# openSX70_ALADDIN_V36_20180117.net
KiCad netlist of a schematic drawn in EAGLE
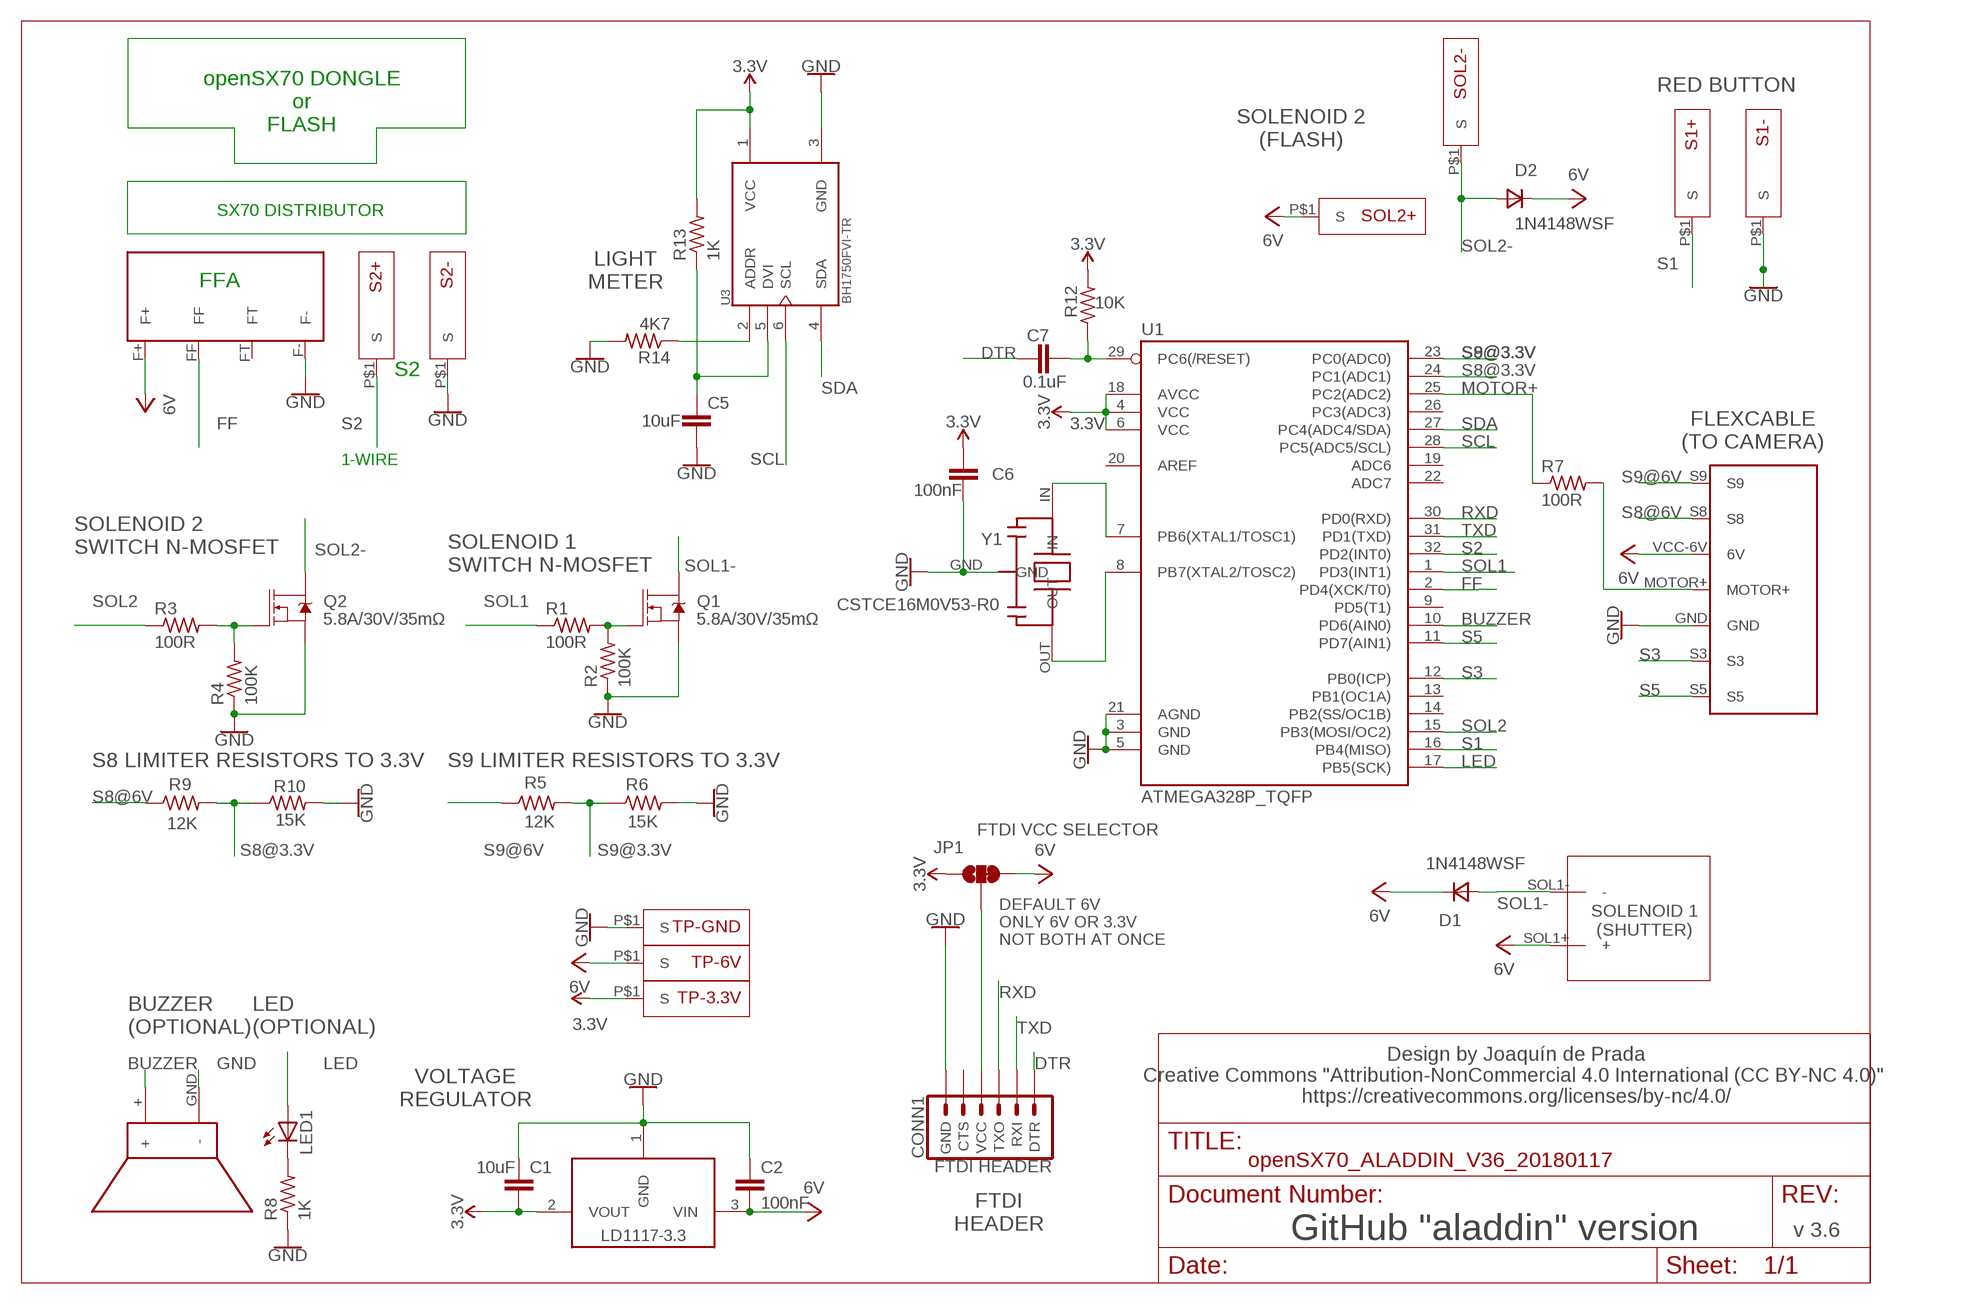
[diagram p0: schematic, sheet 1]

(export (version "E")
  (design (tool "Eeschema 10.0.6"))
  (components
    (comp (ref "BUZZ1")
      (value "CSET8-5G")
      (footprint "eagle-import:CSET8-5G_PACKAGE")
      (libsource (lib "eagle-import") (part "CSET8-5G"))
    )
    (comp (ref "C1")
      (value "10uF")
      (footprint "eagle-import:0603")
      (libsource (lib "eagle-import") (part "10UF-0603-6.3V-20%"))
    )
    (comp (ref "C2")
      (value "100nF")
      (footprint "eagle-import:C0603K")
      (libsource (lib "eagle-import") (part "C-EUC0603K"))
    )
    (comp (ref "C5")
      (value "10uF")
      (footprint "eagle-import:0603")
      (libsource (lib "eagle-import") (part "10UF-0603-6.3V-20%"))
    )
    (comp (ref "C6")
      (value "100nF")
      (footprint "eagle-import:C0805")
      (libsource (lib "eagle-import") (part "resistor_C-EUC0805"))
    )
    (comp (ref "C7")
      (value "0.1uF")
      (footprint "eagle-import:0603")
      (libsource (lib "eagle-import") (part "0.1UF-0603-25V-(+80/-20%)"))
    )
    (comp (ref "CONN1")
      (value "FTDI HEADER")
      (footprint "eagle-import:1X06")
      (libsource (lib "eagle-import") (part "6_PIN_SERIAL_TARGET"))
    )
    (comp (ref "D1")
      (value "1N4148WSF")
      (footprint "eagle-import:SOD323")
      (fields (field (name "MPN") "CDSOD323-T05C"))
      (libsource (lib "eagle-import") (part "DSOD323"))
    )
    (comp (ref "D2")
      (value "1N4148WSF")
      (footprint "eagle-import:SOD323")
      (fields (field (name "MPN") "CDSOD323-T05C"))
      (libsource (lib "eagle-import") (part "DSOD323"))
    )
    (comp (ref "JP1")
      (value "FTDI VCC SELECTOR")
      (footprint "eagle-import:SMT-JUMPER_3_1-NC_TRACE_SILK")
      (libsource (lib "eagle-import") (part "JUMPER-SMT_3_1-NC_TRACE_SILK"))
    )
    (comp (ref "LD11173.3V")
      (value "LD1117 3.3V")
      (footprint "eagle-import:SOT223")
      (fields (field (name "MF") "Advanced Monolithic Systems") (field (name "MP") "AMS1117-5.0"))
      (libsource (lib "eagle-import") (part "LD1117-3.3"))
    )
    (comp (ref "LED1")
      (value "LEDCHIPLED_0805")
      (footprint "eagle-import:CHIPLED_0805")
      (libsource (lib "eagle-import") (part "LEDCHIPLED_0805"))
    )
    (comp (ref "Q1")
      (value "5.8A/30V/35mΩ")
      (footprint "eagle-import:SOT23-3")
      (libsource (lib "eagle-import") (part "MOSFET-NCH-AO3404A"))
    )
    (comp (ref "Q2")
      (value "5.8A/30V/35mΩ")
      (footprint "eagle-import:SOT23-3")
      (libsource (lib "eagle-import") (part "MOSFET-NCH-AO3404A"))
    )
    (comp (ref "R1")
      (value "100R")
      (footprint "eagle-import:R0603")
      (libsource (lib "eagle-import") (part "R-US_R0603"))
    )
    (comp (ref "R2")
      (value "100K")
      (footprint "eagle-import:R0603")
      (libsource (lib "eagle-import") (part "R-US_R0603"))
    )
    (comp (ref "R3")
      (value "100R")
      (footprint "eagle-import:R0603")
      (libsource (lib "eagle-import") (part "R-US_R0603"))
    )
    (comp (ref "R4")
      (value "100K")
      (footprint "eagle-import:R0603")
      (libsource (lib "eagle-import") (part "R-US_R0603"))
    )
    (comp (ref "R5")
      (value "12K")
      (footprint "eagle-import:R0603")
      (libsource (lib "eagle-import") (part "R-US_R0603"))
    )
    (comp (ref "R6")
      (value "15K")
      (footprint "eagle-import:R0603")
      (libsource (lib "eagle-import") (part "R-US_R0603"))
    )
    (comp (ref "R7")
      (value "100R")
      (footprint "eagle-import:R0603")
      (libsource (lib "eagle-import") (part "R-US_R0603"))
    )
    (comp (ref "R8")
      (value "1K")
      (footprint "eagle-import:R0603")
      (libsource (lib "eagle-import") (part "R-US_R0603"))
    )
    (comp (ref "R9")
      (value "12K")
      (footprint "eagle-import:R0603")
      (libsource (lib "eagle-import") (part "R-US_R0603"))
    )
    (comp (ref "R10")
      (value "15K")
      (footprint "eagle-import:R0603")
      (libsource (lib "eagle-import") (part "R-US_R0603"))
    )
    (comp (ref "R12")
      (value "10K")
      (footprint "eagle-import:R0603")
      (libsource (lib "eagle-import") (part "R-US_R0603"))
    )
    (comp (ref "R13")
      (value "1K")
      (footprint "eagle-import:R0603")
      (libsource (lib "eagle-import") (part "R-US_R0603"))
    )
    (comp (ref "R14")
      (value "4K7")
      (footprint "eagle-import:R0603")
      (libsource (lib "eagle-import") (part "R-US_R0603"))
    )
    (comp (ref "S1+")
      (value "SX70-S-PAD-NEW")
      (footprint "eagle-import:SX70-S-PAD2")
      (libsource (lib "eagle-import") (part "SX70-S-PAD-NEW"))
    )
    (comp (ref "S1-")
      (value "SX70-S-PAD-NEW")
      (footprint "eagle-import:SX70-S-PAD2")
      (libsource (lib "eagle-import") (part "SX70-S-PAD-NEW"))
    )
    (comp (ref "S2+")
      (value "SX70-S-PAD-NEW")
      (footprint "eagle-import:SX70-S-PAD2")
      (libsource (lib "eagle-import") (part "SX70-S-PAD-NEW"))
    )
    (comp (ref "S2-")
      (value "SX70-S-PAD-NEW")
      (footprint "eagle-import:SX70-S-PAD2")
      (libsource (lib "eagle-import") (part "SX70-S-PAD-NEW"))
    )
    (comp (ref "SOL1")
      (value "SX70-SOLENOID1-2PADS")
      (footprint "eagle-import:SX70-SOLENOID1-2")
      (libsource (lib "eagle-import") (part "SX70-SOLENOID1-2PADS"))
    )
    (comp (ref "SOL2+")
      (value "SX70-S-PAD-NEW")
      (footprint "eagle-import:SX70-S-PAD2")
      (libsource (lib "eagle-import") (part "SX70-S-PAD-NEW"))
    )
    (comp (ref "SOL2-")
      (value "SX70-S-PAD-NEW")
      (footprint "eagle-import:SX70-S-PAD2")
      (libsource (lib "eagle-import") (part "SX70-S-PAD-NEW"))
    )
    (comp (ref "TP-3.3V")
      (value "SX70-S-PAD-NEW")
      (footprint "eagle-import:SX70-S-PAD2")
      (libsource (lib "eagle-import") (part "SX70-S-PAD-NEW"))
    )
    (comp (ref "TP-6V")
      (value "SX70-S-PAD-NEW")
      (footprint "eagle-import:SX70-S-PAD2")
      (libsource (lib "eagle-import") (part "SX70-S-PAD-NEW"))
    )
    (comp (ref "TP-GND")
      (value "SX70-S-PAD-NEW")
      (footprint "eagle-import:SX70-S-PAD2")
      (libsource (lib "eagle-import") (part "SX70-S-PAD-NEW"))
    )
    (comp (ref "U$1")
      (value "SX70-7-PAD")
      (footprint "eagle-import:SX70-7-PAD")
      (libsource (lib "eagle-import") (part "SX70-7-PAD"))
    )
    (comp (ref "U$2")
      (value "FFA")
      (footprint "eagle-import:FFA-PAD-PACKAGE")
      (libsource (lib "eagle-import") (part "SX70-FFA-PAD"))
    )
    (comp (ref "U1")
      (value "ATMEGA328P_TQFP")
      (footprint "eagle-import:TQFP32-08")
      (libsource (lib "eagle-import") (part "ATMEGA328P_TQFP"))
    )
    (comp (ref "U3")
      (value "BH1750FVI-TR")
      (footprint "eagle-import:SOTFL50P300X75-6N")
      (fields (field (name "MF") "Rohm"))
      (libsource (lib "eagle-import") (part "BH1750FVI-TR"))
    )
    (comp (ref "Y1")
      (value "CSTCE16M0V53-R0")
      (footprint "eagle-import:CFP95P160X100-3N")
      (fields (field (name "MF") "Murata"))
      (libsource (lib "eagle-import") (part "CSTCE16M0V53-R0"))
    )
  )
  (nets
    (net (code "1") (name "/BUZZER") (class "Default")
      (node (ref "BUZZ1") (pin "+") (pinfunction "+_+") (pintype "bidirectional"))
      (node (ref "U1") (pin "10") (pinfunction "PD6(AIN0)_10") (pintype "bidirectional"))
    )
    (net (code "2") (name "/DTR") (class "Default")
      (node (ref "C7") (pin "1") (pinfunction "1_1") (pintype "passive"))
      (node (ref "CONN1") (pin "1") (pinfunction "DTR_1") (pintype "passive"))
    )
    (net (code "3") (name "/FF") (class "Default")
      (node (ref "U$2") (pin "FF") (pinfunction "FF_FF") (pintype "bidirectional"))
      (node (ref "U1") (pin "2") (pinfunction "PD4(XCK/T0)_2") (pintype "bidirectional"))
    )
    (net (code "4") (name "/LED") (class "Default")
      (node (ref "LED1") (pin "A") (pinfunction "A_A") (pintype "passive"))
      (node (ref "U1") (pin "17") (pinfunction "PB5(SCK)_17") (pintype "bidirectional"))
    )
    (net (code "5") (name "/MOTOR+") (class "Default")
      (node (ref "R7") (pin "1") (pinfunction "1_1") (pintype "passive"))
      (node (ref "U1") (pin "25") (pinfunction "PC2(ADC2)_25") (pintype "bidirectional"))
    )
    (net (code "6") (name "/RXD") (class "Default")
      (node (ref "CONN1") (pin "3") (pinfunction "TXO_3") (pintype "passive"))
      (node (ref "U1") (pin "30") (pinfunction "PD0(RXD)_30") (pintype "bidirectional"))
    )
    (net (code "7") (name "/S1") (class "Default")
      (node (ref "S1+") (pin "P$1") (pinfunction "S_P$1") (pintype "bidirectional"))
      (node (ref "U1") (pin "16") (pinfunction "PB4(MISO)_16") (pintype "bidirectional"))
    )
    (net (code "8") (name "/S2") (class "Default")
      (node (ref "S2+") (pin "P$1") (pinfunction "S_P$1") (pintype "bidirectional"))
      (node (ref "U1") (pin "32") (pinfunction "PD2(INT0)_32") (pintype "bidirectional"))
    )
    (net (code "9") (name "/S3") (class "Default")
      (node (ref "U$1") (pin "S3") (pinfunction "S3_S3") (pintype "bidirectional"))
      (node (ref "U1") (pin "12") (pinfunction "PB0(ICP)_12") (pintype "bidirectional"))
    )
    (net (code "10") (name "/S5") (class "Default")
      (node (ref "U$1") (pin "S5") (pinfunction "S5_S5") (pintype "bidirectional"))
      (node (ref "U1") (pin "11") (pinfunction "PD7(AIN1)_11") (pintype "bidirectional"))
    )
    (net (code "11") (name "/S8@3.3V") (class "Default")
      (node (ref "R10") (pin "1") (pinfunction "1_1") (pintype "passive"))
      (node (ref "R9") (pin "2") (pinfunction "2_2") (pintype "passive"))
      (node (ref "U1") (pin "24") (pinfunction "PC1(ADC1)_24") (pintype "bidirectional"))
    )
    (net (code "12") (name "/S8@6V") (class "Default")
      (node (ref "R9") (pin "1") (pinfunction "1_1") (pintype "passive"))
      (node (ref "U$1") (pin "S8") (pinfunction "S8_S8") (pintype "bidirectional"))
    )
    (net (code "13") (name "/S9@3.3V") (class "Default")
      (node (ref "R5") (pin "2") (pinfunction "2_2") (pintype "passive"))
      (node (ref "R6") (pin "1") (pinfunction "1_1") (pintype "passive"))
      (node (ref "U1") (pin "23") (pinfunction "PC0(ADC0)_23") (pintype "bidirectional"))
    )
    (net (code "14") (name "/S9@6V") (class "Default")
      (node (ref "R5") (pin "1") (pinfunction "1_1") (pintype "passive"))
      (node (ref "U$1") (pin "S9") (pinfunction "S9_S9") (pintype "bidirectional"))
    )
    (net (code "15") (name "/SCL") (class "Default")
      (node (ref "U1") (pin "28") (pinfunction "PC5(ADC5/SCL)_28") (pintype "bidirectional"))
      (node (ref "U3") (pin "6") (pinfunction "SCL_6") (pintype "input"))
    )
    (net (code "16") (name "/SDA") (class "Default")
      (node (ref "U1") (pin "27") (pinfunction "PC4(ADC4/SDA)_27") (pintype "bidirectional"))
      (node (ref "U3") (pin "4") (pinfunction "SDA_4") (pintype "bidirectional"))
    )
    (net (code "17") (name "/SOL1") (class "Default")
      (node (ref "R1") (pin "1") (pinfunction "1_1") (pintype "passive"))
      (node (ref "U1") (pin "1") (pinfunction "PD3(INT1)_1") (pintype "bidirectional"))
    )
    (net (code "18") (name "/SOL1-") (class "Default")
      (node (ref "D1") (pin "2") (pinfunction "A_2") (pintype "passive"))
      (node (ref "Q1") (pin "3") (pinfunction "D_3") (pintype "bidirectional"))
      (node (ref "SOL1") (pin "SOL1-") (pinfunction "-_SOL1-") (pintype "bidirectional"))
    )
    (net (code "19") (name "/SOL2") (class "Default")
      (node (ref "R3") (pin "1") (pinfunction "1_1") (pintype "passive"))
      (node (ref "U1") (pin "15") (pinfunction "PB3(MOSI/OC2)_15") (pintype "bidirectional"))
    )
    (net (code "20") (name "/SOL2-") (class "Default")
      (node (ref "D2") (pin "2") (pinfunction "A_2") (pintype "passive"))
      (node (ref "Q2") (pin "3") (pinfunction "D_3") (pintype "bidirectional"))
      (node (ref "SOL2-") (pin "P$1") (pinfunction "S_P$1") (pintype "bidirectional"))
    )
    (net (code "21") (name "/TXD") (class "Default")
      (node (ref "CONN1") (pin "2") (pinfunction "RXI_2") (pintype "passive"))
      (node (ref "U1") (pin "31") (pinfunction "PD1(TXD)_31") (pintype "bidirectional"))
    )
    (net (code "22") (name "3.3V") (class "Default")
      (node (ref "C1") (pin "2") (pinfunction "2_2") (pintype "passive"))
      (node (ref "C6") (pin "1") (pinfunction "1_1") (pintype "passive"))
      (node (ref "JP1") (pin "1") (pinfunction "1_1") (pintype "passive"))
      (node (ref "LD11173.3V") (pin "2") (pinfunction "VOUT_2") (pintype "bidirectional"))
      (node (ref "R12") (pin "2") (pinfunction "2_2") (pintype "passive"))
      (node (ref "R13") (pin "2") (pinfunction "2_2") (pintype "passive"))
      (node (ref "TP-3.3V") (pin "P$1") (pinfunction "S_P$1") (pintype "bidirectional"))
      (node (ref "U1") (pin "18") (pinfunction "AVCC_18") (pintype "bidirectional"))
      (node (ref "U1") (pin "4") (pinfunction "VCC_4") (pintype "bidirectional"))
      (node (ref "U1") (pin "6") (pinfunction "VCC_6") (pintype "bidirectional"))
      (node (ref "U3") (pin "1") (pinfunction "VCC_1") (pintype "power_in"))
    )
    (net (code "23") (name "6V") (class "Default")
      (node (ref "C2") (pin "2") (pinfunction "2_2") (pintype "passive"))
      (node (ref "D1") (pin "1") (pinfunction "C_1") (pintype "passive"))
      (node (ref "D2") (pin "1") (pinfunction "C_1") (pintype "passive"))
      (node (ref "JP1") (pin "3") (pinfunction "3_3") (pintype "passive"))
      (node (ref "LD11173.3V") (pin "3") (pinfunction "VIN_3") (pintype "bidirectional"))
      (node (ref "SOL1") (pin "SOL1+") (pinfunction "+_SOL1+") (pintype "bidirectional"))
      (node (ref "SOL2+") (pin "P$1") (pinfunction "S_P$1") (pintype "bidirectional"))
      (node (ref "TP-6V") (pin "P$1") (pinfunction "S_P$1") (pintype "bidirectional"))
      (node (ref "U$1") (pin "VCC-6V") (pinfunction "6V_VCC-6V") (pintype "bidirectional"))
      (node (ref "U$2") (pin "F+") (pinfunction "F+_F+") (pintype "bidirectional"))
    )
    (net (code "24") (name "GND") (class "Default")
      (node (ref "BUZZ1") (pin "GND") (pinfunction "-_GND") (pintype "bidirectional"))
      (node (ref "C1") (pin "1") (pinfunction "1_1") (pintype "passive"))
      (node (ref "C2") (pin "1") (pinfunction "1_1") (pintype "passive"))
      (node (ref "C5") (pin "2") (pinfunction "2_2") (pintype "passive"))
      (node (ref "C6") (pin "2") (pinfunction "2_2") (pintype "passive"))
      (node (ref "CONN1") (pin "6") (pinfunction "GND_6") (pintype "passive"))
      (node (ref "LD11173.3V") (pin "1") (pinfunction "GND_1") (pintype "bidirectional"))
      (node (ref "Q1") (pin "2") (pinfunction "S_2") (pintype "bidirectional"))
      (node (ref "Q2") (pin "2") (pinfunction "S_2") (pintype "bidirectional"))
      (node (ref "R10") (pin "2") (pinfunction "2_2") (pintype "passive"))
      (node (ref "R14") (pin "2") (pinfunction "2_2") (pintype "passive"))
      (node (ref "R2") (pin "1") (pinfunction "1_1") (pintype "passive"))
      (node (ref "R4") (pin "1") (pinfunction "1_1") (pintype "passive"))
      (node (ref "R6") (pin "2") (pinfunction "2_2") (pintype "passive"))
      (node (ref "R8") (pin "1") (pinfunction "1_1") (pintype "passive"))
      (node (ref "S1-") (pin "P$1") (pinfunction "S_P$1") (pintype "bidirectional"))
      (node (ref "S2-") (pin "P$1") (pinfunction "S_P$1") (pintype "bidirectional"))
      (node (ref "TP-GND") (pin "P$1") (pinfunction "S_P$1") (pintype "bidirectional"))
      (node (ref "U$1") (pin "GND") (pinfunction "GND_GND") (pintype "bidirectional"))
      (node (ref "U$2") (pin "F-") (pinfunction "F-_F-") (pintype "bidirectional"))
      (node (ref "U1") (pin "21") (pinfunction "AGND_21") (pintype "bidirectional"))
      (node (ref "U1") (pin "3") (pinfunction "GND_3") (pintype "bidirectional"))
      (node (ref "U1") (pin "5") (pinfunction "GND_5") (pintype "bidirectional"))
      (node (ref "U3") (pin "3") (pinfunction "GND_3") (pintype "power_in"))
      (node (ref "Y1") (pin "GND") (pinfunction "GND_GND") (pintype "passive"))
    )
    (net (code "25") (name "Net-(CONN1-VCC)") (class "Default")
      (node (ref "CONN1") (pin "4") (pinfunction "VCC_4") (pintype "passive"))
      (node (ref "JP1") (pin "2") (pinfunction "2_2") (pintype "passive"))
    )
    (net (code "26") (name "Net-(LED1-PadC)") (class "Default")
      (node (ref "LED1") (pin "C") (pinfunction "C_C") (pintype "passive"))
      (node (ref "R8") (pin "2") (pinfunction "2_2") (pintype "passive"))
    )
    (net (code "27") (name "Net-(Q1-G)") (class "Default")
      (node (ref "Q1") (pin "1") (pinfunction "G_1") (pintype "bidirectional"))
      (node (ref "R1") (pin "2") (pinfunction "2_2") (pintype "passive"))
      (node (ref "R2") (pin "2") (pinfunction "2_2") (pintype "passive"))
    )
    (net (code "28") (name "Net-(Q2-G)") (class "Default")
      (node (ref "Q2") (pin "1") (pinfunction "G_1") (pintype "bidirectional"))
      (node (ref "R3") (pin "2") (pinfunction "2_2") (pintype "passive"))
      (node (ref "R4") (pin "2") (pinfunction "2_2") (pintype "passive"))
    )
    (net (code "29") (name "Net-(R7-Pad2)") (class "Default")
      (node (ref "R7") (pin "2") (pinfunction "2_2") (pintype "passive"))
      (node (ref "U$1") (pin "MOTOR+") (pinfunction "MOTOR+_MOTOR+") (pintype "bidirectional"))
    )
    (net (code "30") (name "Net-(U1-PB6(XTAL1{slash}TOSC1))") (class "Default")
      (node (ref "U1") (pin "7") (pinfunction "PB6(XTAL1/TOSC1)_7") (pintype "bidirectional"))
      (node (ref "Y1") (pin "IN") (pinfunction "IN_IN") (pintype "input"))
    )
    (net (code "31") (name "Net-(U1-PB7(XTAL2{slash}TOSC2))") (class "Default")
      (node (ref "U1") (pin "8") (pinfunction "PB7(XTAL2/TOSC2)_8") (pintype "bidirectional"))
      (node (ref "Y1") (pin "OUT") (pinfunction "OUT_OUT") (pintype "output"))
    )
    (net (code "32") (name "Net-(U1-PC6({slash}RESET))") (class "Default")
      (node (ref "C7") (pin "2") (pinfunction "2_2") (pintype "passive"))
      (node (ref "R12") (pin "1") (pinfunction "1_1") (pintype "passive"))
      (node (ref "U1") (pin "29") (pinfunction "PC6(/RESET)_29") (pintype "bidirectional"))
    )
    (net (code "33") (name "Net-(U3-ADDR)") (class "Default")
      (node (ref "R14") (pin "1") (pinfunction "1_1") (pintype "passive"))
      (node (ref "U3") (pin "2") (pinfunction "ADDR_2") (pintype "input"))
    )
    (net (code "34") (name "Net-(U3-DVI)") (class "Default")
      (node (ref "C5") (pin "1") (pinfunction "1_1") (pintype "passive"))
      (node (ref "R13") (pin "1") (pinfunction "1_1") (pintype "passive"))
      (node (ref "U3") (pin "5") (pinfunction "DVI_5") (pintype "input"))
    )
    (net (code "35") (name "unconnected-(CONN1-CTS-Pad5)") (class "Default")
      (node (ref "CONN1") (pin "5") (pinfunction "CTS_5") (pintype "passive"))
    )
    (net (code "36") (name "unconnected-(U$2-PadFT)") (class "Default")
      (node (ref "U$2") (pin "FT") (pinfunction "FT_FT") (pintype "bidirectional"))
    )
    (net (code "37") (name "unconnected-(U1-ADC6-Pad19)") (class "Default")
      (node (ref "U1") (pin "19") (pinfunction "ADC6_19") (pintype "bidirectional"))
    )
    (net (code "38") (name "unconnected-(U1-ADC7-Pad22)") (class "Default")
      (node (ref "U1") (pin "22") (pinfunction "ADC7_22") (pintype "bidirectional"))
    )
    (net (code "39") (name "unconnected-(U1-AREF-Pad20)") (class "Default")
      (node (ref "U1") (pin "20") (pinfunction "AREF_20") (pintype "bidirectional"))
    )
    (net (code "40") (name "unconnected-(U1-PB1(OC1A)-Pad13)") (class "Default")
      (node (ref "U1") (pin "13") (pinfunction "PB1(OC1A)_13") (pintype "bidirectional"))
    )
    (net (code "41") (name "unconnected-(U1-PB2(SS{slash}OC1B)-Pad14)") (class "Default")
      (node (ref "U1") (pin "14") (pinfunction "PB2(SS/OC1B)_14") (pintype "bidirectional"))
    )
    (net (code "42") (name "unconnected-(U1-PC3(ADC3)-Pad26)") (class "Default")
      (node (ref "U1") (pin "26") (pinfunction "PC3(ADC3)_26") (pintype "bidirectional"))
    )
    (net (code "43") (name "unconnected-(U1-PD5(T1)-Pad9)") (class "Default")
      (node (ref "U1") (pin "9") (pinfunction "PD5(T1)_9") (pintype "bidirectional"))
    )
  )
)
